# PLC1_4.net
KiCad netlist of a schematic drawn in Altium Designer
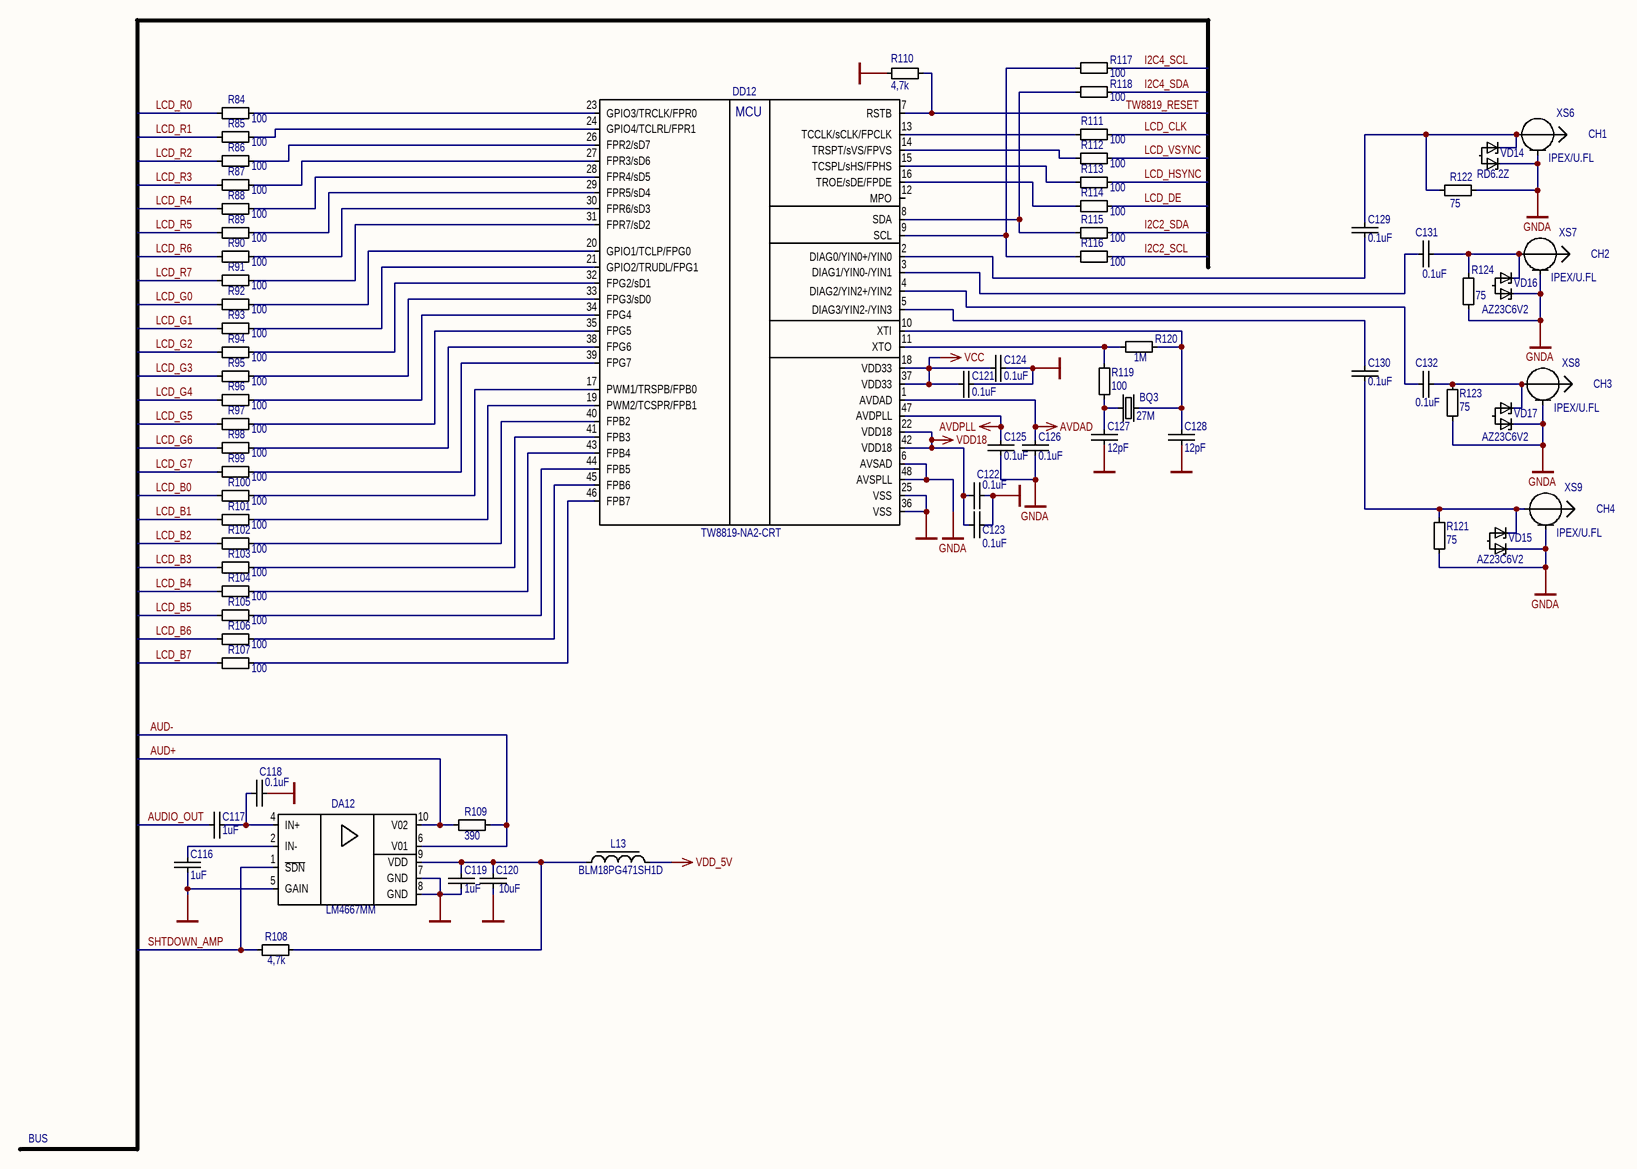
[diagram p0: PLC1_4.SchDoc]

(export (version "E")
  (design (tool "Eeschema 10.0.6"))
  (components
    (comp (ref "BQ3")
      (value "27M")
      (footprint "TSX-3225")
      (fields
        (field (name "MANUFACTURER") "EPSON")
        (field (name "PART NUMBER") "EPSON TSX-3225 27.0000MF10Z-K3")
        (field (name "Comment") "TSX-3225")
      )
      (libsource (lib "PLC1") (part "TSX-3225"))
    )
    (comp (ref "C116")
      (value "1uF")
      (footprint "CAP_0603")
      (fields (field (name "MANUFACTURER") "AVX") (field (name "PART NUMBER") "0603YC105KAT2A"))
      (libsource (lib "PLC1") (part "Cap_0603"))
    )
    (comp (ref "C117")
      (value "1uF")
      (footprint "CAP_0603")
      (fields (field (name "MANUFACTURER") "AVX") (field (name "PART NUMBER") "0603YC105KAT2A"))
      (libsource (lib "PLC1") (part "Cap_0603"))
    )
    (comp (ref "C118")
      (value "0.1uF")
      (footprint "CAP_0603")
      (fields (field (name "MANUFACTURER") "AVX") (field (name "PART NUMBER") "0603YC104KAT2A"))
      (libsource (lib "PLC1") (part "Cap_0603"))
    )
    (comp (ref "C119")
      (value "1uF")
      (footprint "CAP_0603")
      (fields (field (name "MANUFACTURER") "AVX") (field (name "PART NUMBER") "0603YC105KAT2A"))
      (libsource (lib "PLC1") (part "Cap_0603"))
    )
    (comp (ref "C120")
      (value "10uF")
      (footprint "C_0805")
      (fields (field (name "MANUFACTURER") "Murata") (field (name "PART NUMBER") "GRM21BR61E106KA73L"))
      (libsource (lib "PLC1") (part "Cap_0805"))
    )
    (comp (ref "C121")
      (value "0.1uF")
      (footprint "CAP_0603")
      (fields (field (name "MANUFACTURER") "AVX") (field (name "PART NUMBER") "0603YC104KAT2A"))
      (libsource (lib "PLC1") (part "Cap_0603"))
    )
    (comp (ref "C122")
      (value "0.1uF")
      (footprint "CAP_0603")
      (fields (field (name "MANUFACTURER") "AVX") (field (name "PART NUMBER") "0603YC104KAT2A"))
      (libsource (lib "PLC1") (part "Cap_0603"))
    )
    (comp (ref "C123")
      (value "0.1uF")
      (footprint "CAP_0603")
      (fields (field (name "MANUFACTURER") "AVX") (field (name "PART NUMBER") "0603YC104KAT2A"))
      (libsource (lib "PLC1") (part "Cap_0603"))
    )
    (comp (ref "C124")
      (value "0.1uF")
      (footprint "CAP_0603")
      (fields (field (name "MANUFACTURER") "AVX") (field (name "PART NUMBER") "0603YC104KAT2A"))
      (libsource (lib "PLC1") (part "Cap_0603"))
    )
    (comp (ref "C125")
      (value "0.1uF")
      (footprint "CAP_0603")
      (fields (field (name "MANUFACTURER") "AVX") (field (name "PART NUMBER") "0603YC104KAT2A"))
      (libsource (lib "PLC1") (part "Cap_0603"))
    )
    (comp (ref "C126")
      (value "0.1uF")
      (footprint "CAP_0603")
      (fields (field (name "MANUFACTURER") "AVX") (field (name "PART NUMBER") "0603YC104KAT2A"))
      (libsource (lib "PLC1") (part "Cap_0603"))
    )
    (comp (ref "C127")
      (value "12pF")
      (footprint "CAP_0603")
      (fields (field (name "MANUFACTURER") "Murata") (field (name "PART NUMBER") "GRM1885C1H120JA01D"))
      (libsource (lib "PLC1") (part "Cap_0603"))
    )
    (comp (ref "C128")
      (value "12pF")
      (footprint "CAP_0603")
      (fields (field (name "MANUFACTURER") "Murata") (field (name "PART NUMBER") "GRM1885C1H120JA01D"))
      (libsource (lib "PLC1") (part "Cap_0603"))
    )
    (comp (ref "C129")
      (value "0.1uF")
      (footprint "CAP_0603")
      (fields (field (name "MANUFACTURER") "AVX") (field (name "PART NUMBER") "0603YC104KAT2A"))
      (libsource (lib "PLC1") (part "Cap_0603"))
    )
    (comp (ref "C130")
      (value "0.1uF")
      (footprint "CAP_0603")
      (fields (field (name "MANUFACTURER") "AVX") (field (name "PART NUMBER") "0603YC104KAT2A"))
      (libsource (lib "PLC1") (part "Cap_0603"))
    )
    (comp (ref "C131")
      (value "0.1uF")
      (footprint "CAP_0603")
      (fields (field (name "MANUFACTURER") "AVX") (field (name "PART NUMBER") "0603YC104KAT2A"))
      (libsource (lib "PLC1") (part "Cap_0603"))
    )
    (comp (ref "C132")
      (value "0.1uF")
      (footprint "CAP_0603")
      (fields (field (name "MANUFACTURER") "AVX") (field (name "PART NUMBER") "0603YC104KAT2A"))
      (libsource (lib "PLC1") (part "Cap_0603"))
    )
    (comp (ref "DA12")
      (value "LM4667MM")
      (footprint "S-PDSO-G10")
      (description "LM4667MM/NOPB")
      (fields (field (name "MANUFACTURER") "TEXAS INSTRUMENTS"))
      (libsource (lib "PLC1") (part "LM4667MM/NOPB"))
    )
    (comp (ref "DD12")
      (value "TW8819-NA2-CRT")
      (footprint "QFN48.7x7")
      (fields (field (name "MANUFACTURER") "Intersil") (field (name "TW8819-NA2-CRT") "TW8819-NA2-CRT"))
      (libsource (lib "PLC1") (part "TW8819-NA2-CRT"))
    )
    (comp (ref "L13")
      (value "BLM18PG471SH1D")
      (footprint "R_IND_0603")
      (fields (field (name "MANUFACTURER") "Murata"))
      (libsource (lib "PLC1") (part "FCM1608KF-601T03"))
    )
    (comp (ref "R84")
      (value "100")
      (footprint "RES_0402")
      (description "0402")
      (fields (field (name "MANUFACTURER") "BOURNS") (field (name "PART NUMBER") "CR0402-FX-1000GLF"))
      (libsource (lib "PLC1") (part "Res_0402"))
    )
    (comp (ref "R85")
      (value "100")
      (footprint "RES_0402")
      (description "0402")
      (fields (field (name "MANUFACTURER") "BOURNS") (field (name "PART NUMBER") "CR0402-FX-1000GLF"))
      (libsource (lib "PLC1") (part "Res_0402"))
    )
    (comp (ref "R86")
      (value "100")
      (footprint "RES_0402")
      (description "0402")
      (fields (field (name "MANUFACTURER") "BOURNS") (field (name "PART NUMBER") "CR0402-FX-1000GLF"))
      (libsource (lib "PLC1") (part "Res_0402"))
    )
    (comp (ref "R87")
      (value "100")
      (footprint "RES_0402")
      (description "0402")
      (fields (field (name "MANUFACTURER") "BOURNS") (field (name "PART NUMBER") "CR0402-FX-1000GLF"))
      (libsource (lib "PLC1") (part "Res_0402"))
    )
    (comp (ref "R88")
      (value "100")
      (footprint "RES_0402")
      (description "0402")
      (fields (field (name "MANUFACTURER") "BOURNS") (field (name "PART NUMBER") "CR0402-FX-1000GLF"))
      (libsource (lib "PLC1") (part "Res_0402"))
    )
    (comp (ref "R89")
      (value "100")
      (footprint "RES_0402")
      (description "0402")
      (fields (field (name "MANUFACTURER") "BOURNS") (field (name "PART NUMBER") "CR0402-FX-1000GLF"))
      (libsource (lib "PLC1") (part "Res_0402"))
    )
    (comp (ref "R90")
      (value "100")
      (footprint "RES_0402")
      (description "0402")
      (fields (field (name "MANUFACTURER") "BOURNS") (field (name "PART NUMBER") "CR0402-FX-1000GLF"))
      (libsource (lib "PLC1") (part "Res_0402"))
    )
    (comp (ref "R91")
      (value "100")
      (footprint "RES_0402")
      (description "0402")
      (fields (field (name "MANUFACTURER") "BOURNS") (field (name "PART NUMBER") "CR0402-FX-1000GLF"))
      (libsource (lib "PLC1") (part "Res_0402"))
    )
    (comp (ref "R92")
      (value "100")
      (footprint "RES_0402")
      (description "0402")
      (fields (field (name "MANUFACTURER") "BOURNS") (field (name "PART NUMBER") "CR0402-FX-1000GLF"))
      (libsource (lib "PLC1") (part "Res_0402"))
    )
    (comp (ref "R93")
      (value "100")
      (footprint "RES_0402")
      (description "0402")
      (fields (field (name "MANUFACTURER") "BOURNS") (field (name "PART NUMBER") "CR0402-FX-1000GLF"))
      (libsource (lib "PLC1") (part "Res_0402"))
    )
    (comp (ref "R94")
      (value "100")
      (footprint "RES_0402")
      (description "0402")
      (fields (field (name "MANUFACTURER") "BOURNS") (field (name "PART NUMBER") "CR0402-FX-1000GLF"))
      (libsource (lib "PLC1") (part "Res_0402"))
    )
    (comp (ref "R95")
      (value "100")
      (footprint "RES_0402")
      (description "0402")
      (fields (field (name "MANUFACTURER") "BOURNS") (field (name "PART NUMBER") "CR0402-FX-1000GLF"))
      (libsource (lib "PLC1") (part "Res_0402"))
    )
    (comp (ref "R96")
      (value "100")
      (footprint "RES_0402")
      (description "0402")
      (fields (field (name "MANUFACTURER") "BOURNS") (field (name "PART NUMBER") "CR0402-FX-1000GLF"))
      (libsource (lib "PLC1") (part "Res_0402"))
    )
    (comp (ref "R97")
      (value "100")
      (footprint "RES_0402")
      (description "0402")
      (fields (field (name "MANUFACTURER") "BOURNS") (field (name "PART NUMBER") "CR0402-FX-1000GLF"))
      (libsource (lib "PLC1") (part "Res_0402"))
    )
    (comp (ref "R98")
      (value "100")
      (footprint "RES_0402")
      (description "0402")
      (fields (field (name "MANUFACTURER") "BOURNS") (field (name "PART NUMBER") "CR0402-FX-1000GLF"))
      (libsource (lib "PLC1") (part "Res_0402"))
    )
    (comp (ref "R99")
      (value "100")
      (footprint "RES_0402")
      (description "0402")
      (fields (field (name "MANUFACTURER") "BOURNS") (field (name "PART NUMBER") "CR0402-FX-1000GLF"))
      (libsource (lib "PLC1") (part "Res_0402"))
    )
    (comp (ref "R100")
      (value "100")
      (footprint "RES_0402")
      (description "0402")
      (fields (field (name "MANUFACTURER") "BOURNS") (field (name "PART NUMBER") "CR0402-FX-1000GLF"))
      (libsource (lib "PLC1") (part "Res_0402"))
    )
    (comp (ref "R101")
      (value "100")
      (footprint "RES_0402")
      (description "0402")
      (fields (field (name "MANUFACTURER") "BOURNS") (field (name "PART NUMBER") "CR0402-FX-1000GLF"))
      (libsource (lib "PLC1") (part "Res_0402"))
    )
    (comp (ref "R102")
      (value "100")
      (footprint "RES_0402")
      (description "0402")
      (fields (field (name "MANUFACTURER") "BOURNS") (field (name "PART NUMBER") "CR0402-FX-1000GLF"))
      (libsource (lib "PLC1") (part "Res_0402"))
    )
    (comp (ref "R103")
      (value "100")
      (footprint "RES_0402")
      (description "0402")
      (fields (field (name "MANUFACTURER") "BOURNS") (field (name "PART NUMBER") "CR0402-FX-1000GLF"))
      (libsource (lib "PLC1") (part "Res_0402"))
    )
    (comp (ref "R104")
      (value "100")
      (footprint "RES_0402")
      (description "0402")
      (fields (field (name "MANUFACTURER") "BOURNS") (field (name "PART NUMBER") "CR0402-FX-1000GLF"))
      (libsource (lib "PLC1") (part "Res_0402"))
    )
    (comp (ref "R105")
      (value "100")
      (footprint "RES_0402")
      (description "0402")
      (fields (field (name "MANUFACTURER") "BOURNS") (field (name "PART NUMBER") "CR0402-FX-1000GLF"))
      (libsource (lib "PLC1") (part "Res_0402"))
    )
    (comp (ref "R106")
      (value "100")
      (footprint "RES_0402")
      (description "0402")
      (fields (field (name "MANUFACTURER") "BOURNS") (field (name "PART NUMBER") "CR0402-FX-1000GLF"))
      (libsource (lib "PLC1") (part "Res_0402"))
    )
    (comp (ref "R107")
      (value "100")
      (footprint "RES_0402")
      (description "0402")
      (fields (field (name "MANUFACTURER") "BOURNS") (field (name "PART NUMBER") "CR0402-FX-1000GLF"))
      (libsource (lib "PLC1") (part "Res_0402"))
    )
    (comp (ref "R108")
      (value "4,7k")
      (footprint "RES_0603")
      (description "0603, 100")
      (fields (field (name "MANUFACTURER") "Vishay") (field (name "PART NUMBER") "CRCW0603-472JRT1"))
      (libsource (lib "PLC1") (part "Res_0603"))
    )
    (comp (ref "R109")
      (value "390")
      (footprint "RES_0603")
      (description "0603, 390")
      (fields (field (name "MANUFACTURER") "YAGEO") (field (name "PART NUMBER") "RC0603FR-07390RL"))
      (libsource (lib "PLC1") (part "Res_0603"))
    )
    (comp (ref "R110")
      (value "4,7k")
      (footprint "RES_0603")
      (description "0603, 100")
      (fields (field (name "MANUFACTURER") "Vishay") (field (name "PART NUMBER") "CRCW0603-472JRT1"))
      (libsource (lib "PLC1") (part "Res_0603"))
    )
    (comp (ref "R111")
      (value "100")
      (footprint "RES_0402")
      (description "0402")
      (fields (field (name "MANUFACTURER") "BOURNS") (field (name "PART NUMBER") "CR0402-FX-1000GLF"))
      (libsource (lib "PLC1") (part "Res_0402"))
    )
    (comp (ref "R112")
      (value "100")
      (footprint "RES_0402")
      (description "0402")
      (fields (field (name "MANUFACTURER") "BOURNS") (field (name "PART NUMBER") "CR0402-FX-1000GLF"))
      (libsource (lib "PLC1") (part "Res_0402"))
    )
    (comp (ref "R113")
      (value "100")
      (footprint "RES_0402")
      (description "0402")
      (fields (field (name "MANUFACTURER") "BOURNS") (field (name "PART NUMBER") "CR0402-FX-1000GLF"))
      (libsource (lib "PLC1") (part "Res_0402"))
    )
    (comp (ref "R114")
      (value "100")
      (footprint "RES_0402")
      (description "0402")
      (fields (field (name "MANUFACTURER") "BOURNS") (field (name "PART NUMBER") "CR0402-FX-1000GLF"))
      (libsource (lib "PLC1") (part "Res_0402"))
    )
    (comp (ref "R115")
      (value "100")
      (footprint "RES_0402")
      (description "0402")
      (fields (field (name "MANUFACTURER") "BOURNS") (field (name "PART NUMBER") "CR0402-FX-1000GLF"))
      (libsource (lib "PLC1") (part "Res_0402"))
    )
    (comp (ref "R116")
      (value "100")
      (footprint "RES_0402")
      (description "0402")
      (fields (field (name "MANUFACTURER") "BOURNS") (field (name "PART NUMBER") "CR0402-FX-1000GLF"))
      (libsource (lib "PLC1") (part "Res_0402"))
    )
    (comp (ref "R117")
      (value "100")
      (footprint "RES_0402")
      (description "0402")
      (fields (field (name "MANUFACTURER") "BOURNS") (field (name "PART NUMBER") "CR0402-FX-1000GLF"))
      (libsource (lib "PLC1") (part "Res_0402"))
    )
    (comp (ref "R118")
      (value "100")
      (footprint "RES_0402")
      (description "0402")
      (fields (field (name "MANUFACTURER") "BOURNS") (field (name "PART NUMBER") "CR0402-FX-1000GLF"))
      (libsource (lib "PLC1") (part "Res_0402"))
    )
    (comp (ref "R119")
      (value "100")
      (footprint "RES_0402")
      (description "0402")
      (fields (field (name "MANUFACTURER") "BOURNS") (field (name "PART NUMBER") "CR0402-FX-1000GLF"))
      (libsource (lib "PLC1") (part "Res_0402"))
    )
    (comp (ref "R120")
      (value "1M")
      (footprint "RES_0402")
      (description "0402")
      (fields (field (name "MANUFACTURER") "BOURNS") (field (name "PART NUMBER") "RC0402JR-071ML"))
      (libsource (lib "PLC1") (part "Res_0402"))
    )
    (comp (ref "R121")
      (value "75")
      (footprint "RES_0603")
      (description "0603")
      (fields (field (name "MANUFACTURER") "YAGEO") (field (name "PART NUMBER") "RC0603JR-0775RL"))
      (libsource (lib "PLC1") (part "Res_0603"))
    )
    (comp (ref "R122")
      (value "75")
      (footprint "RES_0603")
      (description "0603")
      (fields (field (name "MANUFACTURER") "YAGEO") (field (name "PART NUMBER") "RC0603JR-0775RL"))
      (libsource (lib "PLC1") (part "Res_0603"))
    )
    (comp (ref "R123")
      (value "75")
      (footprint "RES_0603")
      (description "0603")
      (fields (field (name "MANUFACTURER") "YAGEO") (field (name "PART NUMBER") "RC0603JR-0775RL"))
      (libsource (lib "PLC1") (part "Res_0603"))
    )
    (comp (ref "R124")
      (value "75")
      (footprint "RES_0603")
      (description "0603")
      (fields (field (name "MANUFACTURER") "YAGEO") (field (name "PART NUMBER") "RC0603JR-0775RL"))
      (libsource (lib "PLC1") (part "Res_0603"))
    )
    (comp (ref "VD14")
      (value "RD6.2Z")
      (footprint "SC-59")
      (fields (field (name "MANUFACTURER") "NEC"))
      (libsource (lib "PLC1") (part "RD6.2Z"))
    )
    (comp (ref "VD15")
      (value "RD6.2Z")
      (footprint "SC-59")
      (fields (field (name "PART NUMBER") "AZ23C6V2") (field (name "MANUFACTURER") "NEC"))
      (libsource (lib "PLC1") (part "RD6.2Z"))
    )
    (comp (ref "VD16")
      (value "RD6.2Z")
      (footprint "SC-59")
      (fields (field (name "PART NUMBER") "AZ23C6V2") (field (name "MANUFACTURER") "NEC"))
      (libsource (lib "PLC1") (part "RD6.2Z"))
    )
    (comp (ref "VD17")
      (value "RD6.2Z")
      (footprint "SC-59")
      (fields (field (name "PART NUMBER") "AZ23C6V2") (field (name "MANUFACTURER") "NEC"))
      (libsource (lib "PLC1") (part "RD6.2Z"))
    )
    (comp (ref "XS6")
      (value "IPEX/U.FL")
      (footprint "IPEX MHFI")
      (description "IPEX/U.FL male pcb SMT")
      (fields
        (field (name "MANUFACTURER") "taoglas limited")
        (field (name "PACKAGEREFERENCE") "IPEX/U.FL")
        (field (name "PART NUMBER") "20279-001E-01")
      )
      (libsource (lib "PLC1") (part "IPEX/U.FL"))
    )
    (comp (ref "XS7")
      (value "IPEX/U.FL")
      (footprint "IPEX MHFI")
      (description "IPEX/U.FL male pcb SMT")
      (fields
        (field (name "MANUFACTURER") "taoglas limited")
        (field (name "PACKAGEREFERENCE") "IPEX/U.FL")
        (field (name "PART NUMBER") "20279-001E-01")
      )
      (libsource (lib "PLC1") (part "IPEX/U.FL"))
    )
    (comp (ref "XS8")
      (value "IPEX/U.FL")
      (footprint "IPEX MHFI")
      (description "IPEX/U.FL male pcb SMT")
      (fields
        (field (name "MANUFACTURER") "taoglas limited")
        (field (name "PACKAGEREFERENCE") "IPEX/U.FL")
        (field (name "PART NUMBER") "20279-001E-01")
      )
      (libsource (lib "PLC1") (part "IPEX/U.FL"))
    )
    (comp (ref "XS9")
      (value "IPEX/U.FL")
      (footprint "IPEX MHFI")
      (description "IPEX/U.FL male pcb SMT")
      (fields
        (field (name "MANUFACTURER") "taoglas limited")
        (field (name "PACKAGEREFERENCE") "IPEX/U.FL")
        (field (name "PART NUMBER") "20279-001E-01")
      )
      (libsource (lib "PLC1") (part "IPEX/U.FL"))
    )
  )
  (nets
    (net (code "1") (name "/AUD+") (class "Default")
      (node (ref "DA12") (pin "10") (pinfunction "V02_10") (pintype "passive"))
      (node (ref "R109") (pin "2") (pinfunction "2_2") (pintype "passive"))
    )
    (net (code "2") (name "/AUD-") (class "Default")
      (node (ref "DA12") (pin "6") (pinfunction "V01_6") (pintype "passive"))
      (node (ref "R109") (pin "1") (pinfunction "1_1") (pintype "passive"))
    )
    (net (code "3") (name "/AUDIO_OUT") (class "Default")
      (node (ref "C117") (pin "2") (pinfunction "2_2") (pintype "passive"))
    )
    (net (code "4") (name "/I2C2_SCL") (class "Default")
      (node (ref "R116") (pin "2") (pinfunction "2_2") (pintype "passive"))
    )
    (net (code "5") (name "/I2C2_SDA") (class "Default")
      (node (ref "R115") (pin "2") (pinfunction "2_2") (pintype "passive"))
    )
    (net (code "6") (name "/I2C4_SCL") (class "Default")
      (node (ref "R117") (pin "2") (pinfunction "2_2") (pintype "passive"))
    )
    (net (code "7") (name "/I2C4_SDA") (class "Default")
      (node (ref "R118") (pin "2") (pinfunction "2_2") (pintype "passive"))
    )
    (net (code "8") (name "/LCD_B0") (class "Default")
      (node (ref "R100") (pin "2") (pinfunction "2_2") (pintype "passive"))
    )
    (net (code "9") (name "/LCD_B1") (class "Default")
      (node (ref "R101") (pin "2") (pinfunction "2_2") (pintype "passive"))
    )
    (net (code "10") (name "/LCD_B2") (class "Default")
      (node (ref "R102") (pin "2") (pinfunction "2_2") (pintype "passive"))
    )
    (net (code "11") (name "/LCD_B3") (class "Default")
      (node (ref "R103") (pin "2") (pinfunction "2_2") (pintype "passive"))
    )
    (net (code "12") (name "/LCD_B4") (class "Default")
      (node (ref "R104") (pin "2") (pinfunction "2_2") (pintype "passive"))
    )
    (net (code "13") (name "/LCD_B5") (class "Default")
      (node (ref "R105") (pin "2") (pinfunction "2_2") (pintype "passive"))
    )
    (net (code "14") (name "/LCD_B6") (class "Default")
      (node (ref "R106") (pin "2") (pinfunction "2_2") (pintype "passive"))
    )
    (net (code "15") (name "/LCD_B7") (class "Default")
      (node (ref "R107") (pin "2") (pinfunction "2_2") (pintype "passive"))
    )
    (net (code "16") (name "/LCD_CLK") (class "Default")
      (node (ref "R111") (pin "2") (pinfunction "2_2") (pintype "passive"))
    )
    (net (code "17") (name "/LCD_DE") (class "Default")
      (node (ref "R114") (pin "2") (pinfunction "2_2") (pintype "passive"))
    )
    (net (code "18") (name "/LCD_G0") (class "Default")
      (node (ref "R92") (pin "2") (pinfunction "2_2") (pintype "passive"))
    )
    (net (code "19") (name "/LCD_G1") (class "Default")
      (node (ref "R93") (pin "2") (pinfunction "2_2") (pintype "passive"))
    )
    (net (code "20") (name "/LCD_G2") (class "Default")
      (node (ref "R94") (pin "2") (pinfunction "2_2") (pintype "passive"))
    )
    (net (code "21") (name "/LCD_G3") (class "Default")
      (node (ref "R95") (pin "2") (pinfunction "2_2") (pintype "passive"))
    )
    (net (code "22") (name "/LCD_G4") (class "Default")
      (node (ref "R96") (pin "2") (pinfunction "2_2") (pintype "passive"))
    )
    (net (code "23") (name "/LCD_G5") (class "Default")
      (node (ref "R97") (pin "2") (pinfunction "2_2") (pintype "passive"))
    )
    (net (code "24") (name "/LCD_G6") (class "Default")
      (node (ref "R98") (pin "2") (pinfunction "2_2") (pintype "passive"))
    )
    (net (code "25") (name "/LCD_G7") (class "Default")
      (node (ref "R99") (pin "2") (pinfunction "2_2") (pintype "passive"))
    )
    (net (code "26") (name "/LCD_HSYNC") (class "Default")
      (node (ref "R113") (pin "2") (pinfunction "2_2") (pintype "passive"))
    )
    (net (code "27") (name "/LCD_R0") (class "Default")
      (node (ref "R84") (pin "2") (pinfunction "2_2") (pintype "passive"))
    )
    (net (code "28") (name "/LCD_R1") (class "Default")
      (node (ref "R85") (pin "2") (pinfunction "2_2") (pintype "passive"))
    )
    (net (code "29") (name "/LCD_R2") (class "Default")
      (node (ref "R86") (pin "2") (pinfunction "2_2") (pintype "passive"))
    )
    (net (code "30") (name "/LCD_R3") (class "Default")
      (node (ref "R87") (pin "2") (pinfunction "2_2") (pintype "passive"))
    )
    (net (code "31") (name "/LCD_R4") (class "Default")
      (node (ref "R88") (pin "2") (pinfunction "2_2") (pintype "passive"))
    )
    (net (code "32") (name "/LCD_R5") (class "Default")
      (node (ref "R89") (pin "2") (pinfunction "2_2") (pintype "passive"))
    )
    (net (code "33") (name "/LCD_R6") (class "Default")
      (node (ref "R90") (pin "2") (pinfunction "2_2") (pintype "passive"))
    )
    (net (code "34") (name "/LCD_R7") (class "Default")
      (node (ref "R91") (pin "2") (pinfunction "2_2") (pintype "passive"))
    )
    (net (code "35") (name "/LCD_VSYNC") (class "Default")
      (node (ref "R112") (pin "2") (pinfunction "2_2") (pintype "passive"))
    )
    (net (code "36") (name "/SHTDOWN_AMP") (class "Default")
      (node (ref "DA12") (pin "1") (pinfunction "~{SDN}_1") (pintype "passive"))
      (node (ref "R108") (pin "1") (pinfunction "1_1") (pintype "passive"))
    )
    (net (code "37") (name "/TW8819_RESET") (class "Default")
      (node (ref "DD12") (pin "7") (pinfunction "RSTB_7") (pintype "passive"))
      (node (ref "R110") (pin "1") (pinfunction "1_1") (pintype "passive"))
    )
    (net (code "38") (name "AVDAD") (class "Default")
      (node (ref "C126") (pin "1") (pinfunction "1_1") (pintype "passive"))
      (node (ref "DD12") (pin "1") (pinfunction "AVDAD_1") (pintype "passive"))
    )
    (net (code "39") (name "AVDPLL") (class "Default")
      (node (ref "C125") (pin "1") (pinfunction "1_1") (pintype "passive"))
      (node (ref "DD12") (pin "47") (pinfunction "AVDPLL_47") (pintype "passive"))
    )
    (net (code "40") (name "GND") (class "Default")
      (node (ref "C116") (pin "1") (pinfunction "1_1") (pintype "passive"))
      (node (ref "C118") (pin "2") (pinfunction "2_2") (pintype "passive"))
      (node (ref "C119") (pin "1") (pinfunction "1_1") (pintype "passive"))
      (node (ref "C120") (pin "1") (pinfunction "1_1") (pintype "passive"))
      (node (ref "C121") (pin "2") (pinfunction "2_2") (pintype "passive"))
      (node (ref "C122") (pin "2") (pinfunction "2_2") (pintype "passive"))
      (node (ref "C123") (pin "2") (pinfunction "2_2") (pintype "passive"))
      (node (ref "C124") (pin "2") (pinfunction "2_2") (pintype "passive"))
      (node (ref "C127") (pin "1") (pinfunction "1_1") (pintype "passive"))
      (node (ref "C128") (pin "1") (pinfunction "1_1") (pintype "passive"))
      (node (ref "DA12") (pin "5") (pinfunction "GAIN_5") (pintype "passive"))
      (node (ref "DA12") (pin "7") (pinfunction "GND_7") (pintype "passive"))
      (node (ref "DA12") (pin "8") (pinfunction "GND_8") (pintype "passive"))
      (node (ref "DD12") (pin "25") (pinfunction "VSS_25") (pintype "passive"))
      (node (ref "DD12") (pin "36") (pinfunction "VSS_36") (pintype "passive"))
      (node (ref "R110") (pin "2") (pinfunction "2_2") (pintype "passive"))
    )
    (net (code "41") (name "GNDA") (class "Default")
      (node (ref "C125") (pin "2") (pinfunction "2_2") (pintype "passive"))
      (node (ref "C126") (pin "2") (pinfunction "2_2") (pintype "passive"))
      (node (ref "DD12") (pin "48") (pinfunction "AVSPLL_48") (pintype "passive"))
      (node (ref "DD12") (pin "6") (pinfunction "AVSAD_6") (pintype "passive"))
      (node (ref "R121") (pin "1") (pinfunction "1_1") (pintype "passive"))
      (node (ref "R122") (pin "2") (pinfunction "2_2") (pintype "passive"))
      (node (ref "R123") (pin "1") (pinfunction "1_1") (pintype "passive"))
      (node (ref "R124") (pin "2") (pinfunction "2_2") (pintype "passive"))
      (node (ref "VD14") (pin "2") (pinfunction "2_2") (pintype "passive"))
      (node (ref "VD15") (pin "2") (pinfunction "2_2") (pintype "passive"))
      (node (ref "VD16") (pin "2") (pinfunction "2_2") (pintype "passive"))
      (node (ref "VD17") (pin "2") (pinfunction "2_2") (pintype "passive"))
      (node (ref "XS6") (pin "2") (pinfunction "2_2") (pintype "passive"))
      (node (ref "XS7") (pin "2") (pinfunction "2_2") (pintype "passive"))
      (node (ref "XS8") (pin "2") (pinfunction "2_2") (pintype "passive"))
      (node (ref "XS9") (pin "2") (pinfunction "2_2") (pintype "passive"))
    )
    (net (code "42") (name "Net-(BQ3-Pad2)") (class "Default")
      (node (ref "BQ3") (pin "2") (pinfunction "2_2") (pintype "passive"))
      (node (ref "C127") (pin "2") (pinfunction "2_2") (pintype "passive"))
      (node (ref "R119") (pin "1") (pinfunction "1_1") (pintype "passive"))
    )
    (net (code "43") (name "Net-(C129-Pad1)") (class "Default")
      (node (ref "C129") (pin "1") (pinfunction "1_1") (pintype "passive"))
      (node (ref "R122") (pin "1") (pinfunction "1_1") (pintype "passive"))
      (node (ref "VD14") (pin "1") (pinfunction "1_1") (pintype "passive"))
      (node (ref "XS6") (pin "1") (pinfunction "1_1") (pintype "passive"))
    )
    (net (code "44") (name "Net-(C130-Pad2)") (class "Default")
      (node (ref "C130") (pin "2") (pinfunction "2_2") (pintype "passive"))
      (node (ref "R121") (pin "2") (pinfunction "2_2") (pintype "passive"))
      (node (ref "VD15") (pin "1") (pinfunction "1_1") (pintype "passive"))
      (node (ref "XS9") (pin "1") (pinfunction "1_1") (pintype "passive"))
    )
    (net (code "45") (name "Net-(C131-Pad2)") (class "Default")
      (node (ref "C131") (pin "2") (pinfunction "2_2") (pintype "passive"))
      (node (ref "R124") (pin "1") (pinfunction "1_1") (pintype "passive"))
      (node (ref "VD16") (pin "1") (pinfunction "1_1") (pintype "passive"))
      (node (ref "XS7") (pin "1") (pinfunction "1_1") (pintype "passive"))
    )
    (net (code "46") (name "Net-(C132-Pad2)") (class "Default")
      (node (ref "C132") (pin "2") (pinfunction "2_2") (pintype "passive"))
      (node (ref "R123") (pin "2") (pinfunction "2_2") (pintype "passive"))
      (node (ref "VD17") (pin "1") (pinfunction "1_1") (pintype "passive"))
      (node (ref "XS8") (pin "1") (pinfunction "1_1") (pintype "passive"))
    )
    (net (code "47") (name "Net-(DA12-IN+)") (class "Default")
      (node (ref "C117") (pin "1") (pinfunction "1_1") (pintype "passive"))
      (node (ref "C118") (pin "1") (pinfunction "1_1") (pintype "passive"))
      (node (ref "DA12") (pin "4") (pinfunction "IN+_4") (pintype "passive"))
    )
    (net (code "48") (name "Net-(DA12-IN-)") (class "Default")
      (node (ref "C116") (pin "2") (pinfunction "2_2") (pintype "passive"))
      (node (ref "DA12") (pin "2") (pinfunction "IN-_2") (pintype "passive"))
    )
    (net (code "49") (name "Net-(DA12-VDD)") (class "Default")
      (node (ref "C119") (pin "2") (pinfunction "2_2") (pintype "passive"))
      (node (ref "C120") (pin "2") (pinfunction "2_2") (pintype "passive"))
      (node (ref "DA12") (pin "9") (pinfunction "VDD_9") (pintype "passive"))
      (node (ref "L13") (pin "2") (pinfunction "2_2") (pintype "passive"))
      (node (ref "R108") (pin "2") (pinfunction "2_2") (pintype "passive"))
    )
    (net (code "50") (name "Net-(DD12-DIAG0{slash}YIN0+{slash}YIN0)") (class "Default")
      (node (ref "C129") (pin "2") (pinfunction "2_2") (pintype "passive"))
      (node (ref "DD12") (pin "2") (pinfunction "DIAG0/YIN0+/YIN0_2") (pintype "passive"))
    )
    (net (code "51") (name "Net-(DD12-DIAG1{slash}YIN0-{slash}YIN1)") (class "Default")
      (node (ref "C131") (pin "1") (pinfunction "1_1") (pintype "passive"))
      (node (ref "DD12") (pin "3") (pinfunction "DIAG1/YIN0-/YIN1_3") (pintype "passive"))
    )
    (net (code "52") (name "Net-(DD12-DIAG2{slash}YIN2+{slash}YIN2)") (class "Default")
      (node (ref "C132") (pin "1") (pinfunction "1_1") (pintype "passive"))
      (node (ref "DD12") (pin "4") (pinfunction "DIAG2/YIN2+/YIN2_4") (pintype "passive"))
    )
    (net (code "53") (name "Net-(DD12-DIAG3{slash}YIN2-{slash}YIN3)") (class "Default")
      (node (ref "C130") (pin "1") (pinfunction "1_1") (pintype "passive"))
      (node (ref "DD12") (pin "5") (pinfunction "DIAG3/YIN2-/YIN3_5") (pintype "passive"))
    )
    (net (code "54") (name "Net-(DD12-FPB2)") (class "Default")
      (node (ref "DD12") (pin "40") (pinfunction "FPB2_40") (pintype "passive"))
      (node (ref "R102") (pin "1") (pinfunction "1_1") (pintype "passive"))
    )
    (net (code "55") (name "Net-(DD12-FPB3)") (class "Default")
      (node (ref "DD12") (pin "41") (pinfunction "FPB3_41") (pintype "passive"))
      (node (ref "R103") (pin "1") (pinfunction "1_1") (pintype "passive"))
    )
    (net (code "56") (name "Net-(DD12-FPB4)") (class "Default")
      (node (ref "DD12") (pin "43") (pinfunction "FPB4_43") (pintype "passive"))
      (node (ref "R104") (pin "1") (pinfunction "1_1") (pintype "passive"))
    )
    (net (code "57") (name "Net-(DD12-FPB5)") (class "Default")
      (node (ref "DD12") (pin "44") (pinfunction "FPB5_44") (pintype "passive"))
      (node (ref "R105") (pin "1") (pinfunction "1_1") (pintype "passive"))
    )
    (net (code "58") (name "Net-(DD12-FPB6)") (class "Default")
      (node (ref "DD12") (pin "45") (pinfunction "FPB6_45") (pintype "passive"))
      (node (ref "R106") (pin "1") (pinfunction "1_1") (pintype "passive"))
    )
    (net (code "59") (name "Net-(DD12-FPB7)") (class "Default")
      (node (ref "DD12") (pin "46") (pinfunction "FPB7_46") (pintype "passive"))
      (node (ref "R107") (pin "1") (pinfunction "1_1") (pintype "passive"))
    )
    (net (code "60") (name "Net-(DD12-FPG2{slash}sD1)") (class "Default")
      (node (ref "DD12") (pin "32") (pinfunction "FPG2/sD1_32") (pintype "passive"))
      (node (ref "R94") (pin "1") (pinfunction "1_1") (pintype "passive"))
    )
    (net (code "61") (name "Net-(DD12-FPG3{slash}sD0)") (class "Default")
      (node (ref "DD12") (pin "33") (pinfunction "FPG3/sD0_33") (pintype "passive"))
      (node (ref "R95") (pin "1") (pinfunction "1_1") (pintype "passive"))
    )
    (net (code "62") (name "Net-(DD12-FPG4)") (class "Default")
      (node (ref "DD12") (pin "34") (pinfunction "FPG4_34") (pintype "passive"))
      (node (ref "R96") (pin "1") (pinfunction "1_1") (pintype "passive"))
    )
    (net (code "63") (name "Net-(DD12-FPG5)") (class "Default")
      (node (ref "DD12") (pin "35") (pinfunction "FPG5_35") (pintype "passive"))
      (node (ref "R97") (pin "1") (pinfunction "1_1") (pintype "passive"))
    )
    (net (code "64") (name "Net-(DD12-FPG6)") (class "Default")
      (node (ref "DD12") (pin "38") (pinfunction "FPG6_38") (pintype "passive"))
      (node (ref "R98") (pin "1") (pinfunction "1_1") (pintype "passive"))
    )
    (net (code "65") (name "Net-(DD12-FPG7)") (class "Default")
      (node (ref "DD12") (pin "39") (pinfunction "FPG7_39") (pintype "passive"))
      (node (ref "R99") (pin "1") (pinfunction "1_1") (pintype "passive"))
    )
    (net (code "66") (name "Net-(DD12-FPR2{slash}sD7)") (class "Default")
      (node (ref "DD12") (pin "26") (pinfunction "FPR2/sD7_26") (pintype "passive"))
      (node (ref "R86") (pin "1") (pinfunction "1_1") (pintype "passive"))
    )
    (net (code "67") (name "Net-(DD12-FPR3{slash}sD6)") (class "Default")
      (node (ref "DD12") (pin "27") (pinfunction "FPR3/sD6_27") (pintype "passive"))
      (node (ref "R87") (pin "1") (pinfunction "1_1") (pintype "passive"))
    )
    (net (code "68") (name "Net-(DD12-FPR4{slash}sD5)") (class "Default")
      (node (ref "DD12") (pin "28") (pinfunction "FPR4/sD5_28") (pintype "passive"))
      (node (ref "R88") (pin "1") (pinfunction "1_1") (pintype "passive"))
    )
    (net (code "69") (name "Net-(DD12-FPR5{slash}sD4)") (class "Default")
      (node (ref "DD12") (pin "29") (pinfunction "FPR5/sD4_29") (pintype "passive"))
      (node (ref "R89") (pin "1") (pinfunction "1_1") (pintype "passive"))
    )
    (net (code "70") (name "Net-(DD12-FPR6{slash}sD3)") (class "Default")
      (node (ref "DD12") (pin "30") (pinfunction "FPR6/sD3_30") (pintype "passive"))
      (node (ref "R90") (pin "1") (pinfunction "1_1") (pintype "passive"))
    )
    (net (code "71") (name "Net-(DD12-FPR7{slash}sD2)") (class "Default")
      (node (ref "DD12") (pin "31") (pinfunction "FPR7/sD2_31") (pintype "passive"))
      (node (ref "R91") (pin "1") (pinfunction "1_1") (pintype "passive"))
    )
    (net (code "72") (name "Net-(DD12-GPIO1{slash}TCLP{slash}FPG0)") (class "Default")
      (node (ref "DD12") (pin "20") (pinfunction "GPIO1/TCLP/FPG0_20") (pintype "passive"))
      (node (ref "R92") (pin "1") (pinfunction "1_1") (pintype "passive"))
    )
    (net (code "73") (name "Net-(DD12-GPIO2{slash}TRUDL{slash}FPG1)") (class "Default")
      (node (ref "DD12") (pin "21") (pinfunction "GPIO2/TRUDL/FPG1_21") (pintype "passive"))
      (node (ref "R93") (pin "1") (pinfunction "1_1") (pintype "passive"))
    )
    (net (code "74") (name "Net-(DD12-GPIO3{slash}TRCLK{slash}FPR0)") (class "Default")
      (node (ref "DD12") (pin "23") (pinfunction "GPIO3/TRCLK/FPR0_23") (pintype "passive"))
      (node (ref "R84") (pin "1") (pinfunction "1_1") (pintype "passive"))
    )
    (net (code "75") (name "Net-(DD12-GPIO4{slash}TCLRL{slash}FPR1)") (class "Default")
      (node (ref "DD12") (pin "24") (pinfunction "GPIO4/TCLRL/FPR1_24") (pintype "passive"))
      (node (ref "R85") (pin "1") (pinfunction "1_1") (pintype "passive"))
    )
    (net (code "76") (name "Net-(DD12-PWM1{slash}TRSPB{slash}FPB0)") (class "Default")
      (node (ref "DD12") (pin "17") (pinfunction "PWM1/TRSPB/FPB0_17") (pintype "passive"))
      (node (ref "R100") (pin "1") (pinfunction "1_1") (pintype "passive"))
    )
    (net (code "77") (name "Net-(DD12-PWM2{slash}TCSPR{slash}FPB1)") (class "Default")
      (node (ref "DD12") (pin "19") (pinfunction "PWM2/TCSPR/FPB1_19") (pintype "passive"))
      (node (ref "R101") (pin "1") (pinfunction "1_1") (pintype "passive"))
    )
    (net (code "78") (name "Net-(DD12-SCL)") (class "Default")
      (node (ref "DD12") (pin "9") (pinfunction "SCL_9") (pintype "passive"))
      (node (ref "R116") (pin "1") (pinfunction "1_1") (pintype "passive"))
      (node (ref "R117") (pin "1") (pinfunction "1_1") (pintype "passive"))
    )
    (net (code "79") (name "Net-(DD12-SDA)") (class "Default")
      (node (ref "DD12") (pin "8") (pinfunction "SDA_8") (pintype "passive"))
      (node (ref "R115") (pin "1") (pinfunction "1_1") (pintype "passive"))
      (node (ref "R118") (pin "1") (pinfunction "1_1") (pintype "passive"))
    )
    (net (code "80") (name "Net-(DD12-TCCLK{slash}sCLK{slash}FPCLK)") (class "Default")
      (node (ref "DD12") (pin "13") (pinfunction "TCCLK/sCLK/FPCLK_13") (pintype "passive"))
      (node (ref "R111") (pin "1") (pinfunction "1_1") (pintype "passive"))
    )
    (net (code "81") (name "Net-(DD12-TCSPL{slash}sHS{slash}FPHS)") (class "Default")
      (node (ref "DD12") (pin "15") (pinfunction "TCSPL/sHS/FPHS_15") (pintype "passive"))
      (node (ref "R113") (pin "1") (pinfunction "1_1") (pintype "passive"))
    )
    (net (code "82") (name "Net-(DD12-TROE{slash}sDE{slash}FPDE)") (class "Default")
      (node (ref "DD12") (pin "16") (pinfunction "TROE/sDE/FPDE_16") (pintype "passive"))
      (node (ref "R114") (pin "1") (pinfunction "1_1") (pintype "passive"))
    )
    (net (code "83") (name "Net-(DD12-TRSPT{slash}sVS{slash}FPVS)") (class "Default")
      (node (ref "DD12") (pin "14") (pinfunction "TRSPT/sVS/FPVS_14") (pintype "passive"))
      (node (ref "R112") (pin "1") (pinfunction "1_1") (pintype "passive"))
    )
    (net (code "84") (name "Net-(DD12-XTI)") (class "Default")
      (node (ref "BQ3") (pin "1") (pinfunction "1_1") (pintype "passive"))
      (node (ref "C128") (pin "2") (pinfunction "2_2") (pintype "passive"))
      (node (ref "DD12") (pin "10") (pinfunction "XTI_10") (pintype "passive"))
      (node (ref "R120") (pin "1") (pinfunction "1_1") (pintype "passive"))
    )
    (net (code "85") (name "Net-(DD12-XTO)") (class "Default")
      (node (ref "DD12") (pin "11") (pinfunction "XTO_11") (pintype "passive"))
      (node (ref "R119") (pin "2") (pinfunction "2_2") (pintype "passive"))
      (node (ref "R120") (pin "2") (pinfunction "2_2") (pintype "passive"))
    )
    (net (code "86") (name "VCC") (class "Default")
      (node (ref "C121") (pin "1") (pinfunction "1_1") (pintype "passive"))
      (node (ref "C124") (pin "1") (pinfunction "1_1") (pintype "passive"))
      (node (ref "DD12") (pin "18") (pinfunction "VDD33_18") (pintype "passive"))
      (node (ref "DD12") (pin "37") (pinfunction "VDD33_37") (pintype "passive"))
    )
    (net (code "87") (name "VDD18") (class "Default")
      (node (ref "C122") (pin "1") (pinfunction "1_1") (pintype "passive"))
      (node (ref "C123") (pin "1") (pinfunction "1_1") (pintype "passive"))
      (node (ref "DD12") (pin "22") (pinfunction "VDD18_22") (pintype "passive"))
      (node (ref "DD12") (pin "42") (pinfunction "VDD18_42") (pintype "passive"))
    )
    (net (code "88") (name "VDD_5V") (class "Default")
      (node (ref "L13") (pin "1") (pinfunction "1_1") (pintype "passive"))
    )
    (net (code "89") (name "unconnected-(DD12-MPO-Pad12)") (class "Default")
      (node (ref "DD12") (pin "12") (pinfunction "MPO_12") (pintype "passive"))
    )
    (net (code "90") (name "unconnected-(VD14-Pad3)") (class "Default")
      (node (ref "VD14") (pin "3") (pinfunction "3_3") (pintype "passive"))
    )
    (net (code "91") (name "unconnected-(VD15-Pad3)") (class "Default")
      (node (ref "VD15") (pin "3") (pinfunction "3_3") (pintype "passive"))
    )
    (net (code "92") (name "unconnected-(VD16-Pad3)") (class "Default")
      (node (ref "VD16") (pin "3") (pinfunction "3_3") (pintype "passive"))
    )
    (net (code "93") (name "unconnected-(VD17-Pad3)") (class "Default")
      (node (ref "VD17") (pin "3") (pinfunction "3_3") (pintype "passive"))
    )
  )
)
